# HighCurrentLED.net
KiCad netlist of a schematic drawn in Altium Designer
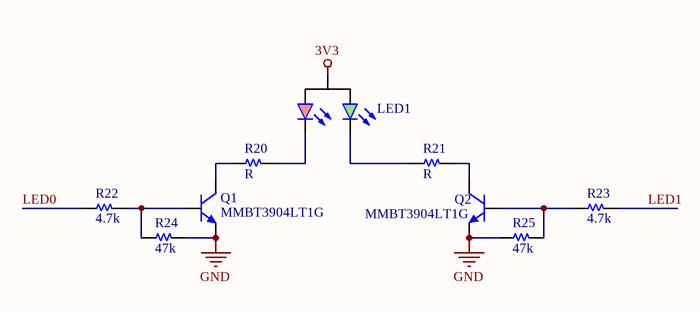
[diagram p0: HighCurrentLED.SchDoc]

(export (version "E")
  (design (tool "Eeschema 10.0.6"))
  (components
    (comp (ref "LED1")
      (value "Led 3pin 2color")
      (footprint "LED 3PIN 2COLOR 5MM")
      (description "Typical LED 3-pin 2-color")
      (libsource (lib "led") (part "Led 3pin 2color"))
    )
    (comp (ref "Q1")
      (value "MMBT3904LT1G")
      (footprint "SOT-23")
      (description "NPN Bipolar Transistor")
      (libsource (lib "chipfc_libs") (part "Transistor NPN"))
    )
    (comp (ref "Q2")
      (value "MMBT3904LT1G")
      (footprint "SOT-23")
      (description "NPN Bipolar Transistor")
      (libsource (lib "chipfc_libs") (part "Transistor NPN"))
    )
    (comp (ref "R20")
      (value "R")
      (footprint "R 0805")
      (description "Resistor")
      (libsource (lib "chipfc_libs") (part "Resistor"))
    )
    (comp (ref "R21")
      (value "R")
      (footprint "R 0805")
      (description "Resistor")
      (libsource (lib "chipfc_libs") (part "Resistor"))
    )
    (comp (ref "R22")
      (value "4.7k")
      (footprint "R 0805")
      (description "Resistor")
      (libsource (lib "chipfc_libs") (part "Resistor"))
    )
    (comp (ref "R23")
      (value "4.7k")
      (footprint "R 0805")
      (description "Resistor")
      (libsource (lib "chipfc_libs") (part "Resistor"))
    )
    (comp (ref "R24")
      (value "47k")
      (footprint "R 0805")
      (description "Resistor")
      (libsource (lib "chipfc_libs") (part "Resistor"))
    )
    (comp (ref "R25")
      (value "47k")
      (footprint "R 0805")
      (description "Resistor")
      (libsource (lib "chipfc_libs") (part "Resistor"))
    )
  )
  (nets
    (net (code "1") (name "/LED0") (class "Default")
      (node (ref "R22") (pin "1") (pinfunction "1_1") (pintype "passive"))
    )
    (net (code "2") (name "/LED1") (class "Default")
      (node (ref "R23") (pin "2") (pinfunction "2_2") (pintype "passive"))
    )
    (net (code "3") (name "3V3") (class "Default")
      (node (ref "LED1") (pin "2") (pinfunction "A_2") (pintype "passive"))
    )
    (net (code "4") (name "GND") (class "Default")
      (node (ref "Q1") (pin "2") (pinfunction "E_2") (pintype "passive"))
      (node (ref "Q2") (pin "2") (pinfunction "E_2") (pintype "passive"))
      (node (ref "R24") (pin "2") (pinfunction "2_2") (pintype "passive"))
      (node (ref "R25") (pin "1") (pinfunction "1_1") (pintype "passive"))
    )
    (net (code "5") (name "Net-(LED1-RK)") (class "Default")
      (node (ref "LED1") (pin "1") (pinfunction "RK_1") (pintype "passive"))
      (node (ref "R20") (pin "2") (pinfunction "2_2") (pintype "passive"))
    )
    (net (code "6") (name "Net-(LED1-YK)") (class "Default")
      (node (ref "LED1") (pin "3") (pinfunction "YK_3") (pintype "passive"))
      (node (ref "R21") (pin "1") (pinfunction "1_1") (pintype "passive"))
    )
    (net (code "7") (name "Net-(Q1-B)") (class "Default")
      (node (ref "Q1") (pin "1") (pinfunction "B_1") (pintype "passive"))
      (node (ref "R22") (pin "2") (pinfunction "2_2") (pintype "passive"))
      (node (ref "R24") (pin "1") (pinfunction "1_1") (pintype "passive"))
    )
    (net (code "8") (name "Net-(Q1-C)") (class "Default")
      (node (ref "Q1") (pin "3") (pinfunction "C_3") (pintype "passive"))
      (node (ref "R20") (pin "1") (pinfunction "1_1") (pintype "passive"))
    )
    (net (code "9") (name "Net-(Q2-B)") (class "Default")
      (node (ref "Q2") (pin "1") (pinfunction "B_1") (pintype "passive"))
      (node (ref "R23") (pin "1") (pinfunction "1_1") (pintype "passive"))
      (node (ref "R25") (pin "2") (pinfunction "2_2") (pintype "passive"))
    )
    (net (code "10") (name "Net-(Q2-C)") (class "Default")
      (node (ref "Q2") (pin "3") (pinfunction "C_3") (pintype "passive"))
      (node (ref "R21") (pin "2") (pinfunction "2_2") (pintype "passive"))
    )
  )
)
